# Sheet1.net
KiCad netlist of a schematic drawn in Altium Designer
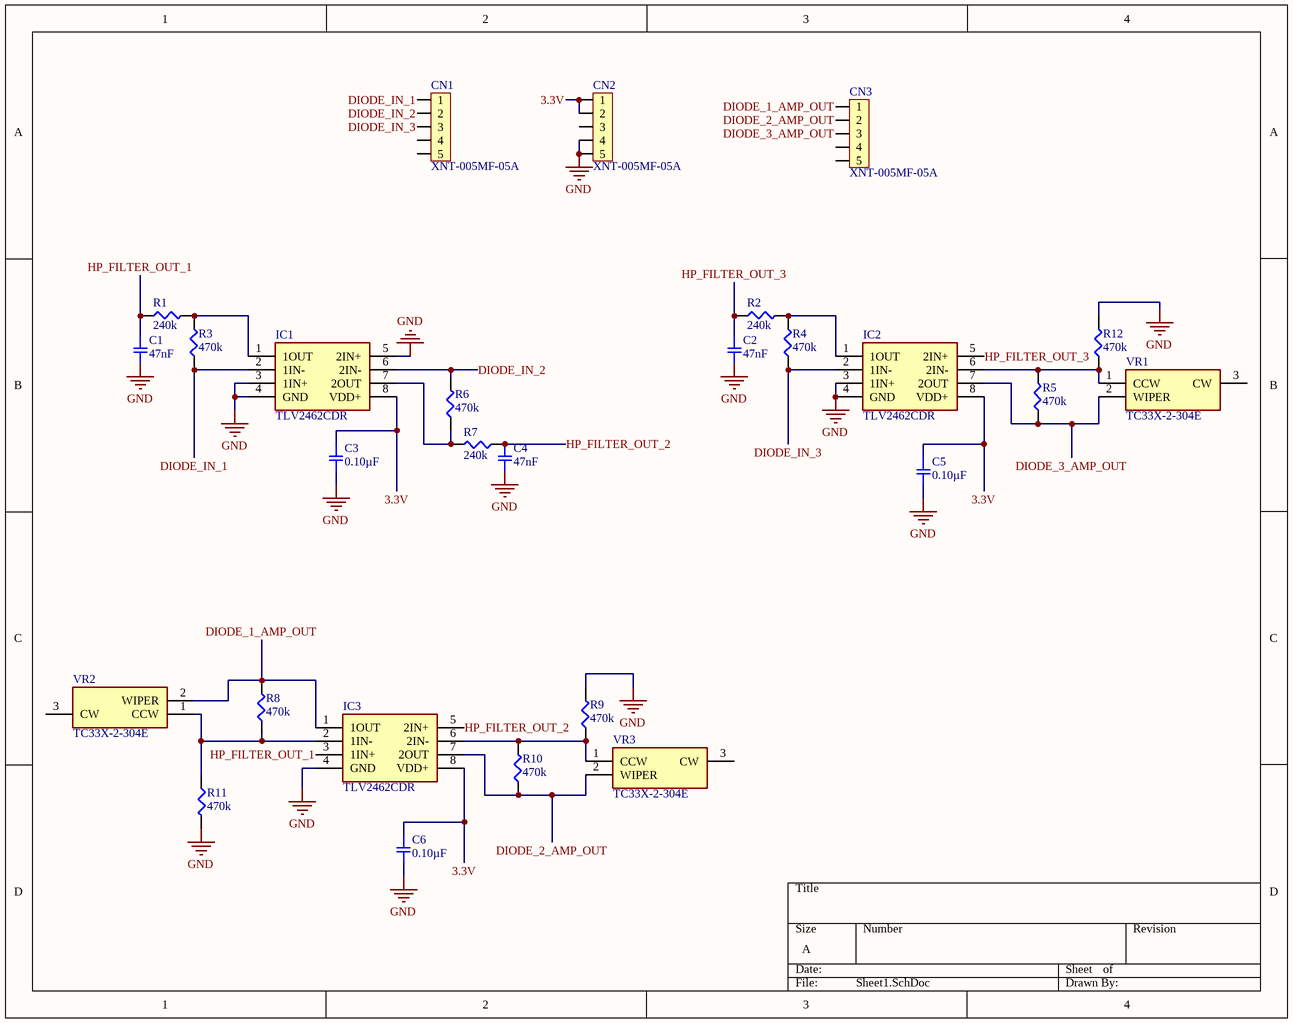
[diagram p0: Sheet1.SchDoc]

(export (version "E")
  (design (tool "Eeschema 10.0.6"))
  (components
    (comp (ref "C1")
      (value "47nF")
      (footprint "SMD-0402C")
      (description "CAP CER 5PF 50V NP0 0402")
      (fields
        (field (name "DIGI-KEY PART NUMBER") "490-8103-1-ND")
        (field (name "PART NUMBER") "GJM1555C1H5R0BB01D")
      )
      (libsource (lib "capacitor_murata_0402") (part "GJM1555C1H5R0BB01D"))
    )
    (comp (ref "C2")
      (value "47nF")
      (footprint "SMD-0402C")
      (description "CAP CER 5PF 50V NP0 0402")
      (fields
        (field (name "DIGI-KEY PART NUMBER") "490-8103-1-ND")
        (field (name "PART NUMBER") "GJM1555C1H5R0BB01D")
      )
      (libsource (lib "capacitor_murata_0402") (part "GJM1555C1H5R0BB01D"))
    )
    (comp (ref "C3")
      (value "0.10µF")
      (footprint "SMD-0402C")
      (description "CAP CER 0.1UF 16V X7R 0402")
      (fields
        (field (name "DIGI-KEY PART NUMBER") "490-4759-1-ND")
        (field (name "PART NUMBER") "GCM155R71C104KA55D")
      )
      (libsource (lib "capacitor_murata_0402") (part "GCM155R71C104KA55D"))
    )
    (comp (ref "C4")
      (value "47nF")
      (footprint "SMD-0402C")
      (description "CAP CER 5PF 50V NP0 0402")
      (fields
        (field (name "DIGI-KEY PART NUMBER") "490-8103-1-ND")
        (field (name "PART NUMBER") "GJM1555C1H5R0BB01D")
      )
      (libsource (lib "capacitor_murata_0402") (part "GJM1555C1H5R0BB01D"))
    )
    (comp (ref "C5")
      (value "0.10µF")
      (footprint "SMD-0402C")
      (description "CAP CER 0.1UF 16V X7R 0402")
      (fields
        (field (name "DIGI-KEY PART NUMBER") "490-4759-1-ND")
        (field (name "PART NUMBER") "GCM155R71C104KA55D")
      )
      (libsource (lib "capacitor_murata_0402") (part "GCM155R71C104KA55D"))
    )
    (comp (ref "C6")
      (value "0.10µF")
      (footprint "SMD-0402C")
      (description "CAP CER 0.1UF 16V X7R 0402")
      (fields
        (field (name "DIGI-KEY PART NUMBER") "490-4759-1-ND")
        (field (name "PART NUMBER") "GCM155R71C104KA55D")
      )
      (libsource (lib "capacitor_murata_0402") (part "GCM155R71C104KA55D"))
    )
    (comp (ref "CN1")
      (value "XNT-005MF-05A")
      (footprint "XNT-005MF-05A")
      (libsource (lib "schematic_components") (part "XNT-005MF-05A"))
    )
    (comp (ref "CN2")
      (value "XNT-005MF-05A")
      (footprint "XNT-005MF-05A")
      (libsource (lib "schematic_components") (part "XNT-005MF-05A"))
    )
    (comp (ref "CN3")
      (value "XNT-005MF-05A")
      (footprint "XNT-005MF-05A")
      (libsource (lib "schematic_components") (part "XNT-005MF-05A"))
    )
    (comp (ref "IC1")
      (value "TLV2462CDR")
      (footprint "SamacSys:SOIC127P600X175-8N")
      (description "Integrated Circuit")
      (fields (field (name "MOUSER PART NUMBER") "595-TLV2462CDR") (field (name "RS PART NUMBER") "6610379"))
      (libsource (lib "*") (part "TLV2462CDR"))
    )
    (comp (ref "IC2")
      (value "TLV2462CDR")
      (footprint "SamacSys:SOIC127P600X175-8N")
      (description "Integrated Circuit")
      (fields (field (name "MOUSER PART NUMBER") "595-TLV2462CDR") (field (name "RS PART NUMBER") "6610379"))
      (libsource (lib "*") (part "TLV2462CDR"))
    )
    (comp (ref "IC3")
      (value "TLV2462CDR")
      (footprint "SamacSys:SOIC127P600X175-8N")
      (description "Integrated Circuit")
      (fields (field (name "MOUSER PART NUMBER") "595-TLV2462CDR") (field (name "RS PART NUMBER") "6610379"))
      (libsource (lib "*") (part "TLV2462CDR"))
    )
    (comp (ref "R1")
      (value "240k")
      (footprint "SMD-0402-RES")
      (description "RES SMD 470K OHM 5% 1/10W 0402")
      (fields (field (name "PART NUMBER") "ERJ-2GEJ104X") (field (name "DIGI-KEY PART NUMBER") "P100KJCT-ND"))
      (libsource (lib "Panasonic_ERJ_0402") (part "ERJ-2GEJ104X"))
    )
    (comp (ref "R2")
      (value "240k")
      (footprint "SMD-0402-RES")
      (description "RES SMD 470K OHM 5% 1/10W 0402")
      (fields (field (name "PART NUMBER") "ERJ-2GEJ104X") (field (name "DIGI-KEY PART NUMBER") "P100KJCT-ND"))
      (libsource (lib "Panasonic_ERJ_0402") (part "ERJ-2GEJ104X"))
    )
    (comp (ref "R3")
      (value "470k")
      (footprint "SMD-0402-RES")
      (description "RES SMD 470K OHM 5% 1/10W 0402")
      (fields (field (name "PART NUMBER") "ERJ-2GEJ104X") (field (name "DIGI-KEY PART NUMBER") "P100KJCT-ND"))
      (libsource (lib "Panasonic_ERJ_0402") (part "ERJ-2GEJ104X"))
    )
    (comp (ref "R4")
      (value "470k")
      (footprint "SMD-0402-RES")
      (description "RES SMD 470K OHM 5% 1/10W 0402")
      (fields (field (name "PART NUMBER") "ERJ-2GEJ104X") (field (name "DIGI-KEY PART NUMBER") "P100KJCT-ND"))
      (libsource (lib "Panasonic_ERJ_0402") (part "ERJ-2GEJ104X"))
    )
    (comp (ref "R5")
      (value "470k")
      (footprint "SMD-0402-RES")
      (description "RES SMD 470K OHM 5% 1/10W 0402")
      (fields (field (name "PART NUMBER") "ERJ-2GEJ104X") (field (name "DIGI-KEY PART NUMBER") "P100KJCT-ND"))
      (libsource (lib "Panasonic_ERJ_0402") (part "ERJ-2GEJ104X"))
    )
    (comp (ref "R6")
      (value "470k")
      (footprint "SMD-0402-RES")
      (description "RES SMD 470K OHM 5% 1/10W 0402")
      (fields (field (name "PART NUMBER") "ERJ-2GEJ104X") (field (name "DIGI-KEY PART NUMBER") "P100KJCT-ND"))
      (libsource (lib "Panasonic_ERJ_0402") (part "ERJ-2GEJ104X"))
    )
    (comp (ref "R7")
      (value "240k")
      (footprint "SMD-0402-RES")
      (description "RES SMD 470K OHM 5% 1/10W 0402")
      (fields (field (name "PART NUMBER") "ERJ-2GEJ104X") (field (name "DIGI-KEY PART NUMBER") "P100KJCT-ND"))
      (libsource (lib "Panasonic_ERJ_0402") (part "ERJ-2GEJ104X"))
    )
    (comp (ref "R8")
      (value "470k")
      (footprint "SMD-0402-RES")
      (description "RES SMD 470K OHM 5% 1/10W 0402")
      (fields (field (name "PART NUMBER") "ERJ-2GEJ104X") (field (name "DIGI-KEY PART NUMBER") "P100KJCT-ND"))
      (libsource (lib "Panasonic_ERJ_0402") (part "ERJ-2GEJ104X"))
    )
    (comp (ref "R9")
      (value "470k")
      (footprint "SMD-0402-RES")
      (description "RES SMD 470K OHM 5% 1/10W 0402")
      (fields (field (name "PART NUMBER") "ERJ-2GEJ104X") (field (name "DIGI-KEY PART NUMBER") "P100KJCT-ND"))
      (libsource (lib "Panasonic_ERJ_0402") (part "ERJ-2GEJ104X"))
    )
    (comp (ref "R10")
      (value "470k")
      (footprint "SMD-0402-RES")
      (description "RES SMD 470K OHM 5% 1/10W 0402")
      (fields (field (name "PART NUMBER") "ERJ-2GEJ104X") (field (name "DIGI-KEY PART NUMBER") "P100KJCT-ND"))
      (libsource (lib "Panasonic_ERJ_0402") (part "ERJ-2GEJ104X"))
    )
    (comp (ref "R11")
      (value "470k")
      (footprint "SMD-0402-RES")
      (description "RES SMD 470K OHM 5% 1/10W 0402")
      (fields (field (name "PART NUMBER") "ERJ-2GEJ104X") (field (name "DIGI-KEY PART NUMBER") "P100KJCT-ND"))
      (libsource (lib "Panasonic_ERJ_0402") (part "ERJ-2GEJ104X"))
    )
    (comp (ref "R12")
      (value "470k")
      (footprint "SMD-0402-RES")
      (description "RES SMD 470K OHM 5% 1/10W 0402")
      (fields (field (name "PART NUMBER") "ERJ-2GEJ104X") (field (name "DIGI-KEY PART NUMBER") "P100KJCT-ND"))
      (libsource (lib "Panasonic_ERJ_0402") (part "ERJ-2GEJ104X"))
    )
    (comp (ref "VR1")
      (value "TC33X-2-304E")
      (footprint "SamacSys:TC33X2304E")
      (description "Variable Resistor")
      (fields (field (name "MOUSER PART NUMBER") "652-TC33X-2-304E"))
      (libsource (lib "*") (part "TC33X-2-304E"))
    )
    (comp (ref "VR2")
      (value "TC33X-2-304E")
      (footprint "SamacSys:TC33X2304E")
      (description "Variable Resistor")
      (fields (field (name "MOUSER PART NUMBER") "652-TC33X-2-304E"))
      (libsource (lib "") (part "TC33X-2-304E_1"))
    )
    (comp (ref "VR3")
      (value "TC33X-2-304E")
      (footprint "SamacSys:TC33X2304E")
      (description "Variable Resistor")
      (fields (field (name "MOUSER PART NUMBER") "652-TC33X-2-304E"))
      (libsource (lib "*") (part "TC33X-2-304E"))
    )
  )
  (nets
    (net (code "1") (name "/3.3V") (class "Default")
      (node (ref "C3") (pin "1") (pinfunction "1_1") (pintype "passive"))
      (node (ref "C5") (pin "1") (pinfunction "1_1") (pintype "passive"))
      (node (ref "C6") (pin "1") (pinfunction "1_1") (pintype "passive"))
      (node (ref "CN2") (pin "1") (pinfunction "1_1") (pintype "passive"))
      (node (ref "CN2") (pin "2") (pinfunction "2_2") (pintype "passive"))
      (node (ref "IC1") (pin "8") (pinfunction "VDD+_8") (pintype "passive"))
      (node (ref "IC2") (pin "8") (pinfunction "VDD+_8") (pintype "passive"))
      (node (ref "IC3") (pin "8") (pinfunction "VDD+_8") (pintype "passive"))
    )
    (net (code "2") (name "/DIODE_1_AMP_OUT") (class "Default")
      (node (ref "CN3") (pin "1") (pinfunction "1_1") (pintype "passive"))
      (node (ref "IC3") (pin "1") (pinfunction "1OUT_1") (pintype "passive"))
      (node (ref "R8") (pin "2") (pinfunction "2_2") (pintype "passive"))
      (node (ref "VR2") (pin "2") (pinfunction "WIPER_2") (pintype "passive"))
    )
    (net (code "3") (name "/DIODE_2_AMP_OUT") (class "Default")
      (node (ref "CN3") (pin "2") (pinfunction "2_2") (pintype "passive"))
      (node (ref "IC3") (pin "7") (pinfunction "2OUT_7") (pintype "passive"))
      (node (ref "R10") (pin "1") (pinfunction "1_1") (pintype "passive"))
      (node (ref "VR3") (pin "2") (pinfunction "WIPER_2") (pintype "passive"))
    )
    (net (code "4") (name "/DIODE_3_AMP_OUT") (class "Default")
      (node (ref "CN3") (pin "3") (pinfunction "3_3") (pintype "passive"))
      (node (ref "IC2") (pin "7") (pinfunction "2OUT_7") (pintype "passive"))
      (node (ref "R5") (pin "1") (pinfunction "1_1") (pintype "passive"))
      (node (ref "VR1") (pin "2") (pinfunction "WIPER_2") (pintype "passive"))
    )
    (net (code "5") (name "/DIODE_IN_1") (class "Default")
      (node (ref "CN1") (pin "1") (pinfunction "1_1") (pintype "passive"))
      (node (ref "IC1") (pin "2") (pinfunction "1IN-_2") (pintype "passive"))
      (node (ref "R3") (pin "1") (pinfunction "1_1") (pintype "passive"))
    )
    (net (code "6") (name "/DIODE_IN_2") (class "Default")
      (node (ref "CN1") (pin "2") (pinfunction "2_2") (pintype "passive"))
      (node (ref "IC1") (pin "6") (pinfunction "2IN-_6") (pintype "passive"))
      (node (ref "R6") (pin "2") (pinfunction "2_2") (pintype "passive"))
    )
    (net (code "7") (name "/DIODE_IN_3") (class "Default")
      (node (ref "CN1") (pin "3") (pinfunction "3_3") (pintype "passive"))
      (node (ref "IC2") (pin "2") (pinfunction "1IN-_2") (pintype "passive"))
      (node (ref "R4") (pin "1") (pinfunction "1_1") (pintype "passive"))
    )
    (net (code "8") (name "/HP_FILTER_OUT_1") (class "Default")
      (node (ref "C1") (pin "1") (pinfunction "1_1") (pintype "passive"))
      (node (ref "IC3") (pin "3") (pinfunction "1IN+_3") (pintype "passive"))
      (node (ref "R1") (pin "1") (pinfunction "1_1") (pintype "passive"))
    )
    (net (code "9") (name "/HP_FILTER_OUT_2") (class "Default")
      (node (ref "C4") (pin "1") (pinfunction "1_1") (pintype "passive"))
      (node (ref "IC3") (pin "5") (pinfunction "2IN+_5") (pintype "passive"))
      (node (ref "R7") (pin "1") (pinfunction "1_1") (pintype "passive"))
    )
    (net (code "10") (name "/HP_FILTER_OUT_3") (class "Default")
      (node (ref "C2") (pin "1") (pinfunction "1_1") (pintype "passive"))
      (node (ref "IC2") (pin "5") (pinfunction "2IN+_5") (pintype "passive"))
      (node (ref "R2") (pin "1") (pinfunction "1_1") (pintype "passive"))
    )
    (net (code "11") (name "GND") (class "Default")
      (node (ref "C1") (pin "2") (pinfunction "2_2") (pintype "passive"))
      (node (ref "C2") (pin "2") (pinfunction "2_2") (pintype "passive"))
      (node (ref "C3") (pin "2") (pinfunction "2_2") (pintype "passive"))
      (node (ref "C4") (pin "2") (pinfunction "2_2") (pintype "passive"))
      (node (ref "C5") (pin "2") (pinfunction "2_2") (pintype "passive"))
      (node (ref "C6") (pin "2") (pinfunction "2_2") (pintype "passive"))
      (node (ref "CN2") (pin "4") (pinfunction "4_4") (pintype "passive"))
      (node (ref "CN2") (pin "5") (pinfunction "5_5") (pintype "passive"))
      (node (ref "IC1") (pin "3") (pinfunction "1IN+_3") (pintype "passive"))
      (node (ref "IC1") (pin "4") (pinfunction "GND_4") (pintype "passive"))
      (node (ref "IC1") (pin "5") (pinfunction "2IN+_5") (pintype "passive"))
      (node (ref "IC2") (pin "3") (pinfunction "1IN+_3") (pintype "passive"))
      (node (ref "IC2") (pin "4") (pinfunction "GND_4") (pintype "passive"))
      (node (ref "IC3") (pin "4") (pinfunction "GND_4") (pintype "passive"))
      (node (ref "R11") (pin "2") (pinfunction "2_2") (pintype "passive"))
      (node (ref "R12") (pin "2") (pinfunction "2_2") (pintype "passive"))
      (node (ref "R9") (pin "2") (pinfunction "2_2") (pintype "passive"))
    )
    (net (code "12") (name "Net-(IC1-1OUT)") (class "Default")
      (node (ref "IC1") (pin "1") (pinfunction "1OUT_1") (pintype "passive"))
      (node (ref "R1") (pin "2") (pinfunction "2_2") (pintype "passive"))
      (node (ref "R3") (pin "2") (pinfunction "2_2") (pintype "passive"))
    )
    (net (code "13") (name "Net-(IC1-2OUT)") (class "Default")
      (node (ref "IC1") (pin "7") (pinfunction "2OUT_7") (pintype "passive"))
      (node (ref "R6") (pin "1") (pinfunction "1_1") (pintype "passive"))
      (node (ref "R7") (pin "2") (pinfunction "2_2") (pintype "passive"))
    )
    (net (code "14") (name "Net-(IC2-1OUT)") (class "Default")
      (node (ref "IC2") (pin "1") (pinfunction "1OUT_1") (pintype "passive"))
      (node (ref "R2") (pin "2") (pinfunction "2_2") (pintype "passive"))
      (node (ref "R4") (pin "2") (pinfunction "2_2") (pintype "passive"))
    )
    (net (code "15") (name "Net-(IC2-2IN-)") (class "Default")
      (node (ref "IC2") (pin "6") (pinfunction "2IN-_6") (pintype "passive"))
      (node (ref "R12") (pin "1") (pinfunction "1_1") (pintype "passive"))
      (node (ref "R5") (pin "2") (pinfunction "2_2") (pintype "passive"))
      (node (ref "VR1") (pin "1") (pinfunction "CCW_1") (pintype "passive"))
    )
    (net (code "16") (name "Net-(IC3-1IN-)") (class "Default")
      (node (ref "IC3") (pin "2") (pinfunction "1IN-_2") (pintype "passive"))
      (node (ref "R11") (pin "1") (pinfunction "1_1") (pintype "passive"))
      (node (ref "R8") (pin "1") (pinfunction "1_1") (pintype "passive"))
      (node (ref "VR2") (pin "1") (pinfunction "CCW_1") (pintype "passive"))
    )
    (net (code "17") (name "Net-(IC3-2IN-)") (class "Default")
      (node (ref "IC3") (pin "6") (pinfunction "2IN-_6") (pintype "passive"))
      (node (ref "R10") (pin "2") (pinfunction "2_2") (pintype "passive"))
      (node (ref "R9") (pin "1") (pinfunction "1_1") (pintype "passive"))
      (node (ref "VR3") (pin "1") (pinfunction "CCW_1") (pintype "passive"))
    )
    (net (code "18") (name "unconnected-(CN1-Pad4)") (class "Default")
      (node (ref "CN1") (pin "4") (pinfunction "4_4") (pintype "passive"))
    )
    (net (code "19") (name "unconnected-(CN1-Pad5)") (class "Default")
      (node (ref "CN1") (pin "5") (pinfunction "5_5") (pintype "passive"))
    )
    (net (code "20") (name "unconnected-(CN2-Pad3)") (class "Default")
      (node (ref "CN2") (pin "3") (pinfunction "3_3") (pintype "passive"))
    )
    (net (code "21") (name "unconnected-(CN3-Pad4)") (class "Default")
      (node (ref "CN3") (pin "4") (pinfunction "4_4") (pintype "passive"))
    )
    (net (code "22") (name "unconnected-(CN3-Pad5)") (class "Default")
      (node (ref "CN3") (pin "5") (pinfunction "5_5") (pintype "passive"))
    )
    (net (code "23") (name "unconnected-(VR1-CW-Pad3)") (class "Default")
      (node (ref "VR1") (pin "3") (pinfunction "CW_3") (pintype "passive"))
    )
    (net (code "24") (name "unconnected-(VR2-CW-Pad3)") (class "Default")
      (node (ref "VR2") (pin "3") (pinfunction "CW_3") (pintype "passive"))
    )
    (net (code "25") (name "unconnected-(VR3-CW-Pad3)") (class "Default")
      (node (ref "VR3") (pin "3") (pinfunction "CW_3") (pintype "passive"))
    )
  )
)
